# Debug.net
KiCad netlist of a schematic drawn in Altium Designer
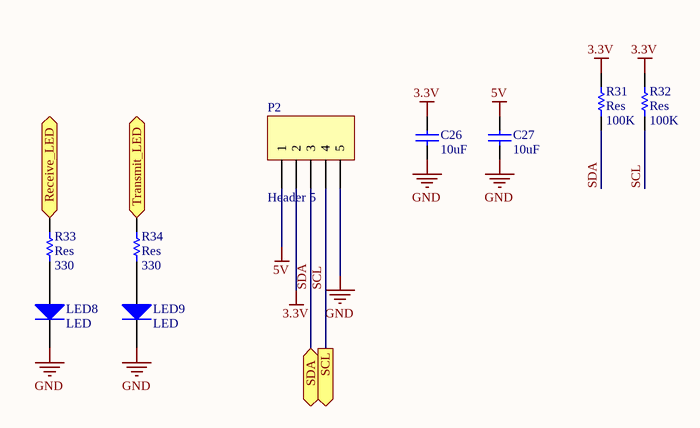
[diagram p0: Debug.SchDoc]

(export (version "E")
  (design (tool "Eeschema 10.0.6"))
  (components
    (comp (ref "C26")
      (value "10uF")
      (footprint "2012[0805]")
      (description "Capacitor")
      (fields (field (name "Comment") "Cap_UP") (field (name "PUBLISHER") "Altium Limited"))
      (libsource (lib "KN2CLib") (part "Cap_UP"))
    )
    (comp (ref "C27")
      (value "10uF")
      (footprint "2012[0805]")
      (description "Capacitor")
      (fields (field (name "Comment") "Cap_UP") (field (name "PUBLISHER") "Altium Limited"))
      (libsource (lib "KN2CLib") (part "Cap_UP"))
    )
    (comp (ref "LED8")
      (value "LED")
      (footprint "2012[0805]")
      (description "1 Amp General Purpose Rectifier")
      (fields (field (name "PUBLISHER") "Altium Limited"))
      (libsource (lib "KN2CLib") (part "Diode"))
    )
    (comp (ref "LED9")
      (value "LED")
      (footprint "2012[0805]")
      (description "1 Amp General Purpose Rectifier")
      (fields (field (name "PUBLISHER") "Altium Limited"))
      (libsource (lib "KN2CLib") (part "Diode"))
    )
    (comp (ref "P2")
      (value "Header 5")
      (footprint "HDR1X5")
      (description "Header, 5-Pin")
      (fields (field (name "PUBLISHER") "Altium Limited"))
      (libsource (lib "Miscellaneous Connectors") (part "Header 5"))
    )
    (comp (ref "R31")
      (value "Res")
      (footprint "2012[0805]")
      (description "Semiconductor Resistor")
      (fields (field (name "ALTIUM_VALUE") "100K") (field (name "PUBLISHER") "Altium Limited"))
      (libsource (lib "KN2CLib") (part "Res"))
    )
    (comp (ref "R32")
      (value "Res")
      (footprint "2012[0805]")
      (description "Semiconductor Resistor")
      (fields (field (name "ALTIUM_VALUE") "100K") (field (name "PUBLISHER") "Altium Limited"))
      (libsource (lib "KN2CLib") (part "Res"))
    )
    (comp (ref "R33")
      (value "Res")
      (footprint "2012[0805]")
      (description "Semiconductor Resistor")
      (fields (field (name "ALTIUM_VALUE") "330") (field (name "PUBLISHER") "Altium Limited"))
      (libsource (lib "KN2CLib") (part "Res"))
    )
    (comp (ref "R34")
      (value "Res")
      (footprint "2012[0805]")
      (description "Semiconductor Resistor")
      (fields (field (name "ALTIUM_VALUE") "330") (field (name "PUBLISHER") "Altium Limited"))
      (libsource (lib "KN2CLib") (part "Res"))
    )
  )
  (nets
    (net (code "1") (name "/Receive_LED") (class "Default")
      (node (ref "R33") (pin "1") (pinfunction "1_1") (pintype "passive"))
    )
    (net (code "2") (name "/SCL") (class "Default")
      (node (ref "P2") (pin "4") (pinfunction "4_4") (pintype "passive"))
      (node (ref "R32") (pin "1") (pinfunction "1_1") (pintype "passive"))
    )
    (net (code "3") (name "/SDA") (class "Default")
      (node (ref "P2") (pin "3") (pinfunction "3_3") (pintype "passive"))
      (node (ref "R31") (pin "1") (pinfunction "1_1") (pintype "passive"))
    )
    (net (code "4") (name "/Transmit_LED") (class "Default")
      (node (ref "R34") (pin "1") (pinfunction "1_1") (pintype "passive"))
    )
    (net (code "5") (name "3.3V") (class "Default")
      (node (ref "C26") (pin "2") (pinfunction "2_2") (pintype "passive"))
      (node (ref "P2") (pin "2") (pinfunction "2_2") (pintype "passive"))
      (node (ref "R31") (pin "2") (pinfunction "2_2") (pintype "passive"))
      (node (ref "R32") (pin "2") (pinfunction "2_2") (pintype "passive"))
    )
    (net (code "6") (name "5V") (class "Default")
      (node (ref "C27") (pin "2") (pinfunction "2_2") (pintype "passive"))
      (node (ref "P2") (pin "1") (pinfunction "1_1") (pintype "passive"))
    )
    (net (code "7") (name "GND") (class "Default")
      (node (ref "C26") (pin "1") (pinfunction "1_1") (pintype "passive"))
      (node (ref "C27") (pin "1") (pinfunction "1_1") (pintype "passive"))
      (node (ref "LED8") (pin "2") (pinfunction "K_2") (pintype "passive"))
      (node (ref "LED9") (pin "2") (pinfunction "K_2") (pintype "passive"))
      (node (ref "P2") (pin "5") (pinfunction "5_5") (pintype "passive"))
    )
    (net (code "8") (name "Net-(LED8-A)") (class "Default")
      (node (ref "LED8") (pin "1") (pinfunction "A_1") (pintype "passive"))
      (node (ref "R33") (pin "2") (pinfunction "2_2") (pintype "passive"))
    )
    (net (code "9") (name "Net-(LED9-A)") (class "Default")
      (node (ref "LED9") (pin "1") (pinfunction "A_1") (pintype "passive"))
      (node (ref "R34") (pin "2") (pinfunction "2_2") (pintype "passive"))
    )
  )
)
